# motherboard.net
KiCad netlist of a schematic drawn in EAGLE
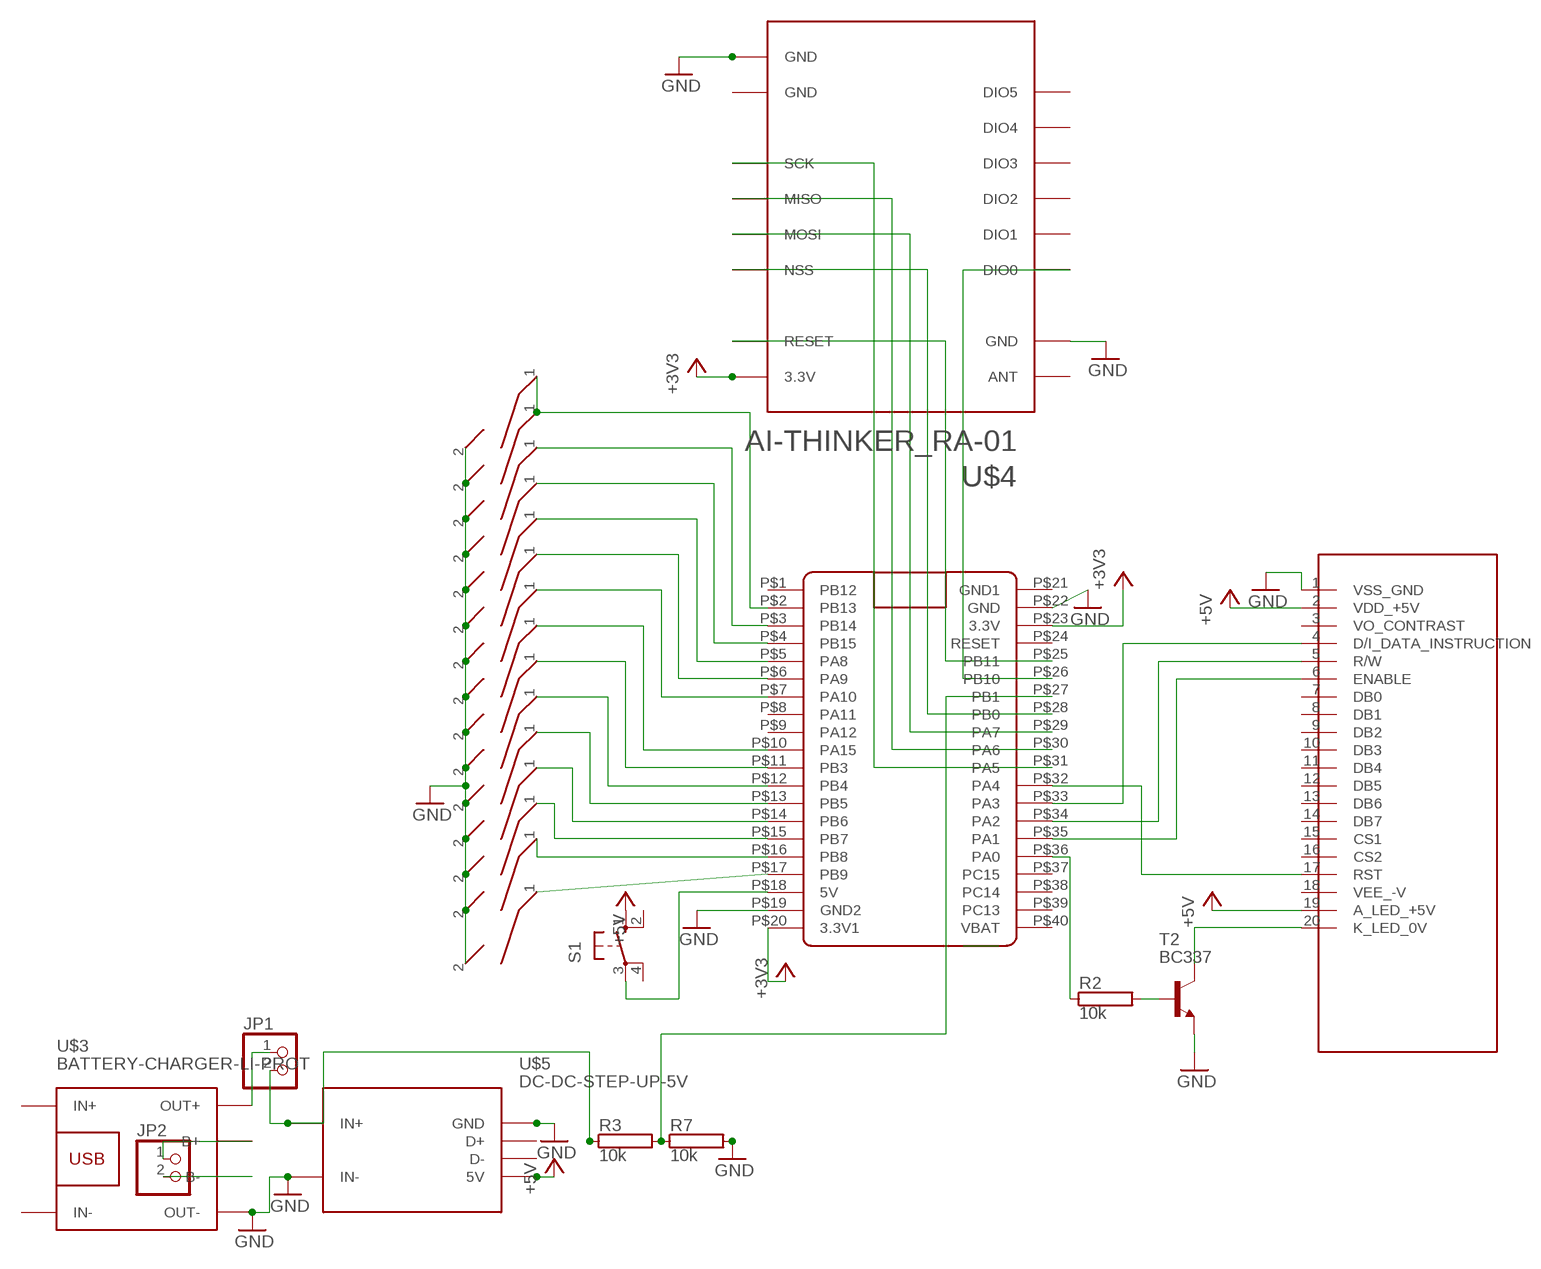
[diagram p0: schematic, sheet 1]

(export (version "E")
  (design (tool "Eeschema 10.0.6"))
  (components
    (comp (ref "JP1")
      (value "PINHD-1X2/90")
      (footprint "eagle-import:1X02_90")
      (libsource (lib "eagle-import") (part "PINHD-1X2/90"))
    )
    (comp (ref "JP2")
      (value "PINHD-1X2/90")
      (footprint "eagle-import:1X02_90")
      (libsource (lib "eagle-import") (part "PINHD-1X2/90"))
    )
    (comp (ref "R2")
      (value "10k")
      (footprint "eagle-import:AC01")
      (libsource (lib "eagle-import") (part "RAC01"))
    )
    (comp (ref "R3")
      (value "10k")
      (footprint "eagle-import:AC01")
      (libsource (lib "eagle-import") (part "RAC01"))
    )
    (comp (ref "R7")
      (value "10k")
      (footprint "eagle-import:AC01")
      (libsource (lib "eagle-import") (part "RAC01"))
    )
    (comp (ref "S1")
      (value "10-XX")
      (footprint "eagle-import:B3F-10XX")
      (fields (field (name "MPN") "B3F-1000"))
      (libsource (lib "eagle-import") (part "10-XX"))
    )
    (comp (ref "SW1")
      (value "CHERRY_MX")
      (footprint "eagle-import:MX1A-XXNN")
      (libsource (lib "eagle-import") (part "CHERRY_MX"))
    )
    (comp (ref "SW2")
      (value "CHERRY_MX")
      (footprint "eagle-import:MX1A-XXNN")
      (libsource (lib "eagle-import") (part "CHERRY_MX"))
    )
    (comp (ref "SW3")
      (value "CHERRY_MX")
      (footprint "eagle-import:MX1A-XXNN")
      (libsource (lib "eagle-import") (part "CHERRY_MX"))
    )
    (comp (ref "SW4")
      (value "CHERRY_MX")
      (footprint "eagle-import:MX1A-XXNN")
      (libsource (lib "eagle-import") (part "CHERRY_MX"))
    )
    (comp (ref "SW5")
      (value "CHERRY_MX")
      (footprint "eagle-import:MX1A-XXNN")
      (libsource (lib "eagle-import") (part "CHERRY_MX"))
    )
    (comp (ref "SW6")
      (value "CHERRY_MX")
      (footprint "eagle-import:MX1A-XXNN")
      (libsource (lib "eagle-import") (part "CHERRY_MX"))
    )
    (comp (ref "SW7")
      (value "CHERRY_MX")
      (footprint "eagle-import:MX1A-XXNN")
      (libsource (lib "eagle-import") (part "CHERRY_MX"))
    )
    (comp (ref "SW8")
      (value "CHERRY_MX")
      (footprint "eagle-import:MX1A-XXNN")
      (libsource (lib "eagle-import") (part "CHERRY_MX"))
    )
    (comp (ref "SW9")
      (value "CHERRY_MX")
      (footprint "eagle-import:MX1A-XXNN")
      (libsource (lib "eagle-import") (part "CHERRY_MX"))
    )
    (comp (ref "SW10")
      (value "CHERRY_MX")
      (footprint "eagle-import:MX1A-XXNN")
      (libsource (lib "eagle-import") (part "CHERRY_MX"))
    )
    (comp (ref "SW11")
      (value "CHERRY_MX")
      (footprint "eagle-import:MX1A-XXNN")
      (libsource (lib "eagle-import") (part "CHERRY_MX"))
    )
    (comp (ref "SW12")
      (value "CHERRY_MX")
      (footprint "eagle-import:MX1A-XXNN")
      (libsource (lib "eagle-import") (part "CHERRY_MX"))
    )
    (comp (ref "SW13")
      (value "CHERRY_MX")
      (footprint "eagle-import:MX1A-XXNN")
      (libsource (lib "eagle-import") (part "CHERRY_MX"))
    )
    (comp (ref "SW14")
      (value "CHERRY_MX")
      (footprint "eagle-import:MX1A-XXNN")
      (libsource (lib "eagle-import") (part "CHERRY_MX"))
    )
    (comp (ref "SW15")
      (value "CHERRY_MX")
      (footprint "eagle-import:MX1A-XXNN")
      (libsource (lib "eagle-import") (part "CHERRY_MX"))
    )
    (comp (ref "T2")
      (value "BC337")
      (footprint "eagle-import:TO92")
      (libsource (lib "eagle-import") (part "BC337"))
    )
    (comp (ref "U$1")
      (value "W12864")
      (footprint "eagle-import:W12864")
      (libsource (lib "eagle-import") (part "W12864"))
    )
    (comp (ref "U$2")
      (value "BLUE_PILL")
      (footprint "eagle-import:BLUE_PILL")
      (libsource (lib "eagle-import") (part "BLUE_PILL"))
    )
    (comp (ref "U$3")
      (value "BATTERY-CHARGER-LI-PROT")
      (footprint "eagle-import:BATTERY-CHARGER-LI-PROT")
      (libsource (lib "eagle-import") (part "BATTERY-CHARGER-LI-PROT"))
    )
    (comp (ref "U$4")
      (value "AI-THINKER_RA-01")
      (footprint "eagle-import:AI-THINKER_RA-01")
      (libsource (lib "eagle-import") (part "AI-THINKER_RA-01"))
    )
    (comp (ref "U$5")
      (value "DC-DC-STEP-UP-5V")
      (footprint "eagle-import:DC-DC-STEP-UP-5V")
      (libsource (lib "eagle-import") (part "DC-DC-STEP-UP-5V"))
    )
  )
  (nets
    (net (code "1") (name "+3V3") (class "Default")
      (node (ref "U$2") (pin "P$20") (pinfunction "3.3V1_P$20") (pintype "bidirectional"))
      (node (ref "U$2") (pin "P$23") (pinfunction "3.3V_P$23") (pintype "bidirectional"))
      (node (ref "U$4") (pin "P$3") (pinfunction "3.3V_P$3") (pintype "bidirectional"))
    )
    (net (code "2") (name "+5V") (class "Default")
      (node (ref "S1") (pin "1") (pinfunction "S_1") (pintype "passive"))
      (node (ref "U$1") (pin "19") (pinfunction "A_LED_+5V_19") (pintype "bidirectional"))
      (node (ref "U$1") (pin "2") (pinfunction "VDD_+5V_2") (pintype "bidirectional"))
      (node (ref "U$5") (pin "5V") (pinfunction "5V_5V") (pintype "bidirectional"))
    )
    (net (code "3") (name "/GND1") (class "Default")
      (node (ref "U$2") (pin "P$21") (pinfunction "GND1_P$21") (pintype "power_in"))
    )
    (net (code "4") (name "GND") (class "Default")
      (node (ref "R7") (pin "2") (pinfunction "2_2") (pintype "passive"))
      (node (ref "SW1") (pin "2") (pinfunction "2_2") (pintype "passive"))
      (node (ref "SW10") (pin "2") (pinfunction "2_2") (pintype "passive"))
      (node (ref "SW11") (pin "2") (pinfunction "2_2") (pintype "passive"))
      (node (ref "SW12") (pin "2") (pinfunction "2_2") (pintype "passive"))
      (node (ref "SW13") (pin "2") (pinfunction "2_2") (pintype "passive"))
      (node (ref "SW14") (pin "2") (pinfunction "2_2") (pintype "passive"))
      (node (ref "SW15") (pin "2") (pinfunction "2_2") (pintype "passive"))
      (node (ref "SW2") (pin "2") (pinfunction "2_2") (pintype "passive"))
      (node (ref "SW3") (pin "2") (pinfunction "2_2") (pintype "passive"))
      (node (ref "SW4") (pin "2") (pinfunction "2_2") (pintype "passive"))
      (node (ref "SW5") (pin "2") (pinfunction "2_2") (pintype "passive"))
      (node (ref "SW6") (pin "2") (pinfunction "2_2") (pintype "passive"))
      (node (ref "SW7") (pin "2") (pinfunction "2_2") (pintype "passive"))
      (node (ref "SW8") (pin "2") (pinfunction "2_2") (pintype "passive"))
      (node (ref "SW9") (pin "2") (pinfunction "2_2") (pintype "passive"))
      (node (ref "T2") (pin "1") (pinfunction "E_1") (pintype "passive"))
      (node (ref "U$1") (pin "1") (pinfunction "VSS_GND_1") (pintype "bidirectional"))
      (node (ref "U$2") (pin "P$19") (pinfunction "GND2_P$19") (pintype "bidirectional"))
      (node (ref "U$2") (pin "P$22") (pinfunction "GND_P$22") (pintype "bidirectional"))
      (node (ref "U$3") (pin "OUT-") (pinfunction "OUT-_OUT-") (pintype "bidirectional"))
      (node (ref "U$4") (pin "P$16") (pinfunction "GND_P$16") (pintype "bidirectional"))
      (node (ref "U$4") (pin "P$2") (pinfunction "GND_P$2") (pintype "bidirectional"))
      (node (ref "U$5") (pin "GND") (pinfunction "GND_GND") (pintype "bidirectional"))
      (node (ref "U$5") (pin "IN-") (pinfunction "IN-_IN-") (pintype "power_in"))
    )
    (net (code "5") (name "Net-(JP1-Pad1)") (class "Default")
      (node (ref "JP1") (pin "1") (pinfunction "1_1") (pintype "passive"))
      (node (ref "U$3") (pin "OUT+") (pinfunction "OUT+_OUT+") (pintype "bidirectional"))
    )
    (net (code "6") (name "Net-(JP1-Pad2)") (class "Default")
      (node (ref "JP1") (pin "2") (pinfunction "2_2") (pintype "passive"))
      (node (ref "R3") (pin "1") (pinfunction "1_1") (pintype "passive"))
      (node (ref "U$5") (pin "IN+") (pinfunction "IN+_IN+") (pintype "power_in"))
    )
    (net (code "7") (name "Net-(JP2-Pad1)") (class "Default")
      (node (ref "JP2") (pin "1") (pinfunction "1_1") (pintype "passive"))
      (node (ref "U$3") (pin "B+") (pinfunction "B+_B+") (pintype "bidirectional"))
    )
    (net (code "8") (name "Net-(JP2-Pad2)") (class "Default")
      (node (ref "JP2") (pin "2") (pinfunction "2_2") (pintype "passive"))
      (node (ref "U$3") (pin "B-") (pinfunction "B-_B-") (pintype "bidirectional"))
    )
    (net (code "9") (name "Net-(S1-P)") (class "Default")
      (node (ref "S1") (pin "3") (pinfunction "P_3") (pintype "passive"))
      (node (ref "U$2") (pin "P$18") (pinfunction "5V_P$18") (pintype "bidirectional"))
    )
    (net (code "10") (name "Net-(T2-B)") (class "Default")
      (node (ref "R2") (pin "2") (pinfunction "2_2") (pintype "passive"))
      (node (ref "T2") (pin "2") (pinfunction "B_2") (pintype "passive"))
    )
    (net (code "11") (name "Net-(T2-C)") (class "Default")
      (node (ref "T2") (pin "3") (pinfunction "C_3") (pintype "passive"))
      (node (ref "U$1") (pin "20") (pinfunction "K_LED_0V_20") (pintype "bidirectional"))
    )
    (net (code "12") (name "Net-(U$1-D{slash}I_DATA_INSTRUCTION)") (class "Default")
      (node (ref "U$1") (pin "4") (pinfunction "D/I_DATA_INSTRUCTION_4") (pintype "bidirectional"))
      (node (ref "U$2") (pin "P$33") (pinfunction "PA3_P$33") (pintype "bidirectional"))
    )
    (net (code "13") (name "Net-(U$1-ENABLE)") (class "Default")
      (node (ref "U$1") (pin "6") (pinfunction "ENABLE_6") (pintype "bidirectional"))
      (node (ref "U$2") (pin "P$35") (pinfunction "PA1_P$35") (pintype "bidirectional"))
    )
    (net (code "14") (name "Net-(U$1-RST)") (class "Default")
      (node (ref "U$1") (pin "17") (pinfunction "RST_17") (pintype "bidirectional"))
      (node (ref "U$2") (pin "P$32") (pinfunction "PA4_P$32") (pintype "bidirectional"))
    )
    (net (code "15") (name "Net-(U$1-R{slash}W)") (class "Default")
      (node (ref "U$1") (pin "5") (pinfunction "R/W_5") (pintype "bidirectional"))
      (node (ref "U$2") (pin "P$34") (pinfunction "PA2_P$34") (pintype "bidirectional"))
    )
    (net (code "16") (name "Net-(U$2-PA0)") (class "Default")
      (node (ref "R2") (pin "1") (pinfunction "1_1") (pintype "passive"))
      (node (ref "U$2") (pin "P$36") (pinfunction "PA0_P$36") (pintype "bidirectional"))
    )
    (net (code "17") (name "Net-(U$2-PA5)") (class "Default")
      (node (ref "U$2") (pin "P$31") (pinfunction "PA5_P$31") (pintype "bidirectional"))
      (node (ref "U$4") (pin "P$12") (pinfunction "SCK_P$12") (pintype "bidirectional"))
    )
    (net (code "18") (name "Net-(U$2-PA6)") (class "Default")
      (node (ref "U$2") (pin "P$30") (pinfunction "PA6_P$30") (pintype "bidirectional"))
      (node (ref "U$4") (pin "P$13") (pinfunction "MISO_P$13") (pintype "bidirectional"))
    )
    (net (code "19") (name "Net-(U$2-PA7)") (class "Default")
      (node (ref "U$2") (pin "P$29") (pinfunction "PA7_P$29") (pintype "bidirectional"))
      (node (ref "U$4") (pin "P$14") (pinfunction "MOSI_P$14") (pintype "bidirectional"))
    )
    (net (code "20") (name "Net-(U$2-PA8)") (class "Default")
      (node (ref "SW11") (pin "1") (pinfunction "1_1") (pintype "passive"))
      (node (ref "U$2") (pin "P$5") (pinfunction "PA8_P$5") (pintype "bidirectional"))
    )
    (net (code "21") (name "Net-(U$2-PA9)") (class "Default")
      (node (ref "SW10") (pin "1") (pinfunction "1_1") (pintype "passive"))
      (node (ref "U$2") (pin "P$6") (pinfunction "PA9_P$6") (pintype "bidirectional"))
    )
    (net (code "22") (name "Net-(U$2-PA10)") (class "Default")
      (node (ref "SW9") (pin "1") (pinfunction "1_1") (pintype "passive"))
      (node (ref "U$2") (pin "P$7") (pinfunction "PA10_P$7") (pintype "bidirectional"))
    )
    (net (code "23") (name "Net-(U$2-PA15)") (class "Default")
      (node (ref "SW8") (pin "1") (pinfunction "1_1") (pintype "passive"))
      (node (ref "U$2") (pin "P$10") (pinfunction "PA15_P$10") (pintype "bidirectional"))
    )
    (net (code "24") (name "Net-(U$2-PB0)") (class "Default")
      (node (ref "U$2") (pin "P$28") (pinfunction "PB0_P$28") (pintype "bidirectional"))
      (node (ref "U$4") (pin "P$15") (pinfunction "NSS_P$15") (pintype "bidirectional"))
    )
    (net (code "25") (name "Net-(U$2-PB1)") (class "Default")
      (node (ref "R3") (pin "2") (pinfunction "2_2") (pintype "passive"))
      (node (ref "R7") (pin "1") (pinfunction "1_1") (pintype "passive"))
      (node (ref "U$2") (pin "P$27") (pinfunction "PB1_P$27") (pintype "bidirectional"))
    )
    (net (code "26") (name "Net-(U$2-PB3)") (class "Default")
      (node (ref "SW7") (pin "1") (pinfunction "1_1") (pintype "passive"))
      (node (ref "U$2") (pin "P$11") (pinfunction "PB3_P$11") (pintype "bidirectional"))
    )
    (net (code "27") (name "Net-(U$2-PB4)") (class "Default")
      (node (ref "SW6") (pin "1") (pinfunction "1_1") (pintype "passive"))
      (node (ref "U$2") (pin "P$12") (pinfunction "PB4_P$12") (pintype "bidirectional"))
    )
    (net (code "28") (name "Net-(U$2-PB5)") (class "Default")
      (node (ref "SW5") (pin "1") (pinfunction "1_1") (pintype "passive"))
      (node (ref "U$2") (pin "P$13") (pinfunction "PB5_P$13") (pintype "bidirectional"))
    )
    (net (code "29") (name "Net-(U$2-PB6)") (class "Default")
      (node (ref "SW4") (pin "1") (pinfunction "1_1") (pintype "passive"))
      (node (ref "U$2") (pin "P$14") (pinfunction "PB6_P$14") (pintype "bidirectional"))
    )
    (net (code "30") (name "Net-(U$2-PB7)") (class "Default")
      (node (ref "SW3") (pin "1") (pinfunction "1_1") (pintype "passive"))
      (node (ref "U$2") (pin "P$15") (pinfunction "PB7_P$15") (pintype "bidirectional"))
    )
    (net (code "31") (name "Net-(U$2-PB8)") (class "Default")
      (node (ref "SW2") (pin "1") (pinfunction "1_1") (pintype "passive"))
      (node (ref "U$2") (pin "P$16") (pinfunction "PB8_P$16") (pintype "bidirectional"))
    )
    (net (code "32") (name "Net-(U$2-PB9)") (class "Default")
      (node (ref "SW1") (pin "1") (pinfunction "1_1") (pintype "passive"))
      (node (ref "U$2") (pin "P$17") (pinfunction "PB9_P$17") (pintype "bidirectional"))
    )
    (net (code "33") (name "Net-(U$2-PB10)") (class "Default")
      (node (ref "U$2") (pin "P$26") (pinfunction "PB10_P$26") (pintype "bidirectional"))
      (node (ref "U$4") (pin "P$5") (pinfunction "DIO0_P$5") (pintype "bidirectional"))
    )
    (net (code "34") (name "Net-(U$2-PB11)") (class "Default")
      (node (ref "U$2") (pin "P$25") (pinfunction "PB11_P$25") (pintype "bidirectional"))
      (node (ref "U$4") (pin "P$4") (pinfunction "RESET_P$4") (pintype "bidirectional"))
    )
    (net (code "35") (name "Net-(U$2-PB13)") (class "Default")
      (node (ref "SW14") (pin "1") (pinfunction "1_1") (pintype "passive"))
      (node (ref "SW15") (pin "1") (pinfunction "1_1") (pintype "passive"))
      (node (ref "U$2") (pin "P$2") (pinfunction "PB13_P$2") (pintype "bidirectional"))
    )
    (net (code "36") (name "Net-(U$2-PB14)") (class "Default")
      (node (ref "SW13") (pin "1") (pinfunction "1_1") (pintype "passive"))
      (node (ref "U$2") (pin "P$3") (pinfunction "PB14_P$3") (pintype "bidirectional"))
    )
    (net (code "37") (name "Net-(U$2-PB15)") (class "Default")
      (node (ref "SW12") (pin "1") (pinfunction "1_1") (pintype "passive"))
      (node (ref "U$2") (pin "P$4") (pinfunction "PB15_P$4") (pintype "bidirectional"))
    )
    (net (code "38") (name "unconnected-(S1-P1-Pad4)") (class "Default")
      (node (ref "S1") (pin "4") (pinfunction "P1_4") (pintype "passive"))
    )
    (net (code "39") (name "unconnected-(S1-S1-Pad2)") (class "Default")
      (node (ref "S1") (pin "2") (pinfunction "S1_2") (pintype "passive"))
    )
    (net (code "40") (name "unconnected-(U$1-CS1-Pad15)") (class "Default")
      (node (ref "U$1") (pin "15") (pinfunction "CS1_15") (pintype "bidirectional"))
    )
    (net (code "41") (name "unconnected-(U$1-CS2-Pad16)") (class "Default")
      (node (ref "U$1") (pin "16") (pinfunction "CS2_16") (pintype "bidirectional"))
    )
    (net (code "42") (name "unconnected-(U$1-DB0-Pad7)") (class "Default")
      (node (ref "U$1") (pin "7") (pinfunction "DB0_7") (pintype "bidirectional"))
    )
    (net (code "43") (name "unconnected-(U$1-DB1-Pad8)") (class "Default")
      (node (ref "U$1") (pin "8") (pinfunction "DB1_8") (pintype "bidirectional"))
    )
    (net (code "44") (name "unconnected-(U$1-DB2-Pad9)") (class "Default")
      (node (ref "U$1") (pin "9") (pinfunction "DB2_9") (pintype "bidirectional"))
    )
    (net (code "45") (name "unconnected-(U$1-DB3-Pad10)") (class "Default")
      (node (ref "U$1") (pin "10") (pinfunction "DB3_10") (pintype "bidirectional"))
    )
    (net (code "46") (name "unconnected-(U$1-DB4-Pad11)") (class "Default")
      (node (ref "U$1") (pin "11") (pinfunction "DB4_11") (pintype "bidirectional"))
    )
    (net (code "47") (name "unconnected-(U$1-DB5-Pad12)") (class "Default")
      (node (ref "U$1") (pin "12") (pinfunction "DB5_12") (pintype "bidirectional"))
    )
    (net (code "48") (name "unconnected-(U$1-DB6-Pad13)") (class "Default")
      (node (ref "U$1") (pin "13") (pinfunction "DB6_13") (pintype "bidirectional"))
    )
    (net (code "49") (name "unconnected-(U$1-DB7-Pad14)") (class "Default")
      (node (ref "U$1") (pin "14") (pinfunction "DB7_14") (pintype "bidirectional"))
    )
    (net (code "50") (name "unconnected-(U$1-VEE_-V-Pad18)") (class "Default")
      (node (ref "U$1") (pin "18") (pinfunction "VEE_-V_18") (pintype "bidirectional"))
    )
    (net (code "51") (name "unconnected-(U$1-VO_CONTRAST-Pad3)") (class "Default")
      (node (ref "U$1") (pin "3") (pinfunction "VO_CONTRAST_3") (pintype "bidirectional"))
    )
    (net (code "52") (name "unconnected-(U$2-PA11-PadP$8)") (class "Default")
      (node (ref "U$2") (pin "P$8") (pinfunction "PA11_P$8") (pintype "bidirectional"))
    )
    (net (code "53") (name "unconnected-(U$2-PA12-PadP$9)") (class "Default")
      (node (ref "U$2") (pin "P$9") (pinfunction "PA12_P$9") (pintype "bidirectional"))
    )
    (net (code "54") (name "unconnected-(U$2-PB12-PadP$1)") (class "Default")
      (node (ref "U$2") (pin "P$1") (pinfunction "PB12_P$1") (pintype "bidirectional"))
    )
    (net (code "55") (name "unconnected-(U$2-PC13-PadP$39)") (class "Default")
      (node (ref "U$2") (pin "P$39") (pinfunction "PC13_P$39") (pintype "bidirectional"))
    )
    (net (code "56") (name "unconnected-(U$2-PC14-PadP$38)") (class "Default")
      (node (ref "U$2") (pin "P$38") (pinfunction "PC14_P$38") (pintype "bidirectional"))
    )
    (net (code "57") (name "unconnected-(U$2-PC15-PadP$37)") (class "Default")
      (node (ref "U$2") (pin "P$37") (pinfunction "PC15_P$37") (pintype "bidirectional"))
    )
    (net (code "58") (name "unconnected-(U$2-RESET-PadP$24)") (class "Default")
      (node (ref "U$2") (pin "P$24") (pinfunction "RESET_P$24") (pintype "bidirectional"))
    )
    (net (code "59") (name "unconnected-(U$2-VBAT-PadP$40)") (class "Default")
      (node (ref "U$2") (pin "P$40") (pinfunction "VBAT_P$40") (pintype "bidirectional"))
    )
    (net (code "60") (name "unconnected-(U$3-PadIN+)") (class "Default")
      (node (ref "U$3") (pin "IN+") (pinfunction "IN+_IN+") (pintype "bidirectional"))
    )
    (net (code "61") (name "unconnected-(U$3-PadIN-)") (class "Default")
      (node (ref "U$3") (pin "IN-") (pinfunction "IN-_IN-") (pintype "bidirectional"))
    )
    (net (code "62") (name "unconnected-(U$4-ANT-PadP$1)") (class "Default")
      (node (ref "U$4") (pin "P$1") (pinfunction "ANT_P$1") (pintype "bidirectional"))
    )
    (net (code "63") (name "unconnected-(U$4-DIO1-PadP$6)") (class "Default")
      (node (ref "U$4") (pin "P$6") (pinfunction "DIO1_P$6") (pintype "bidirectional"))
    )
    (net (code "64") (name "unconnected-(U$4-DIO2-PadP$7)") (class "Default")
      (node (ref "U$4") (pin "P$7") (pinfunction "DIO2_P$7") (pintype "bidirectional"))
    )
    (net (code "65") (name "unconnected-(U$4-DIO3-PadP$8)") (class "Default")
      (node (ref "U$4") (pin "P$8") (pinfunction "DIO3_P$8") (pintype "bidirectional"))
    )
    (net (code "66") (name "unconnected-(U$4-DIO4-PadP$10)") (class "Default")
      (node (ref "U$4") (pin "P$10") (pinfunction "DIO4_P$10") (pintype "bidirectional"))
    )
    (net (code "67") (name "unconnected-(U$4-DIO5-PadP$11)") (class "Default")
      (node (ref "U$4") (pin "P$11") (pinfunction "DIO5_P$11") (pintype "bidirectional"))
    )
    (net (code "68") (name "unconnected-(U$4-GND-PadP$9)") (class "Default")
      (node (ref "U$4") (pin "P$9") (pinfunction "GND_P$9") (pintype "bidirectional"))
    )
    (net (code "69") (name "unconnected-(U$5-PadD+)") (class "Default")
      (node (ref "U$5") (pin "D+") (pinfunction "D+_D+") (pintype "bidirectional"))
    )
    (net (code "70") (name "unconnected-(U$5-PadD-)") (class "Default")
      (node (ref "U$5") (pin "D-") (pinfunction "D-_D-") (pintype "bidirectional"))
    )
  )
)
